# Power_Supply.net
KiCad netlist of a schematic drawn in Altium Designer
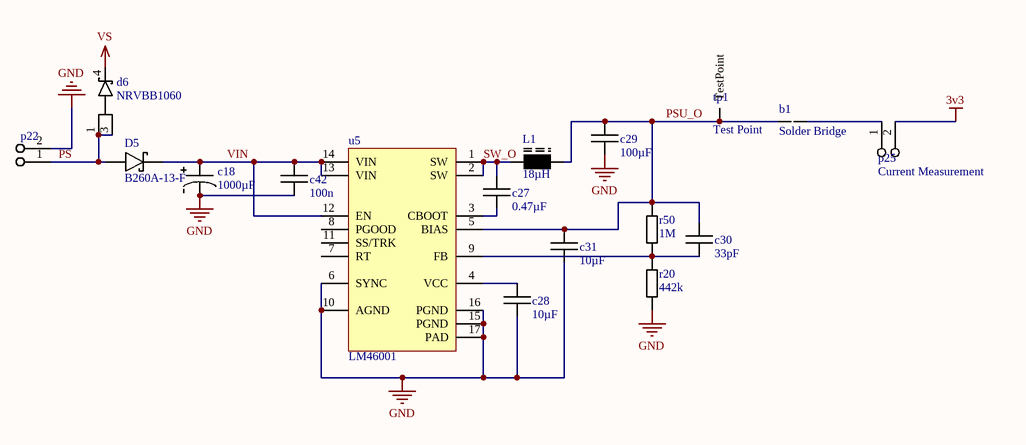
[diagram p0: Power Supply.SchDoc]

(export (version "E")
  (design (tool "Eeschema 10.0.6"))
  (components
    (comp (ref "b1")
      (value "Solder Bridge")
      (footprint "Solder Bridge")
      (libsource (lib "Board_Props") (part "Solder Bridge"))
    )
    (comp (ref "c18")
      (value "1000µF")
      (footprint "TH Elco 16")
      (description "d = 16mm")
      (libsource (lib "Panasonic") (part "Elco TH d16"))
    )
    (comp (ref "c27")
      (value "0.47µF")
      (footprint "0805")
      (description "...F")
      (libsource (lib "Generic R-C") (part "0805 Capacitor"))
    )
    (comp (ref "c28")
      (value "10µF")
      (footprint "0603")
      (description "...F")
      (libsource (lib "Generic R-C") (part "0603 Capacitor"))
    )
    (comp (ref "c29")
      (value "100µF")
      (footprint "1210")
      (description "C1210C107M8PACTU")
      (libsource (lib "KEMET MLCC") (part "1210 Capacitor"))
    )
    (comp (ref "c30")
      (value "33pF")
      (footprint "0603")
      (description "...F")
      (libsource (lib "Generic R-C") (part "0603 Capacitor"))
    )
    (comp (ref "c31")
      (value "10µF")
      (footprint "0603")
      (description "...F")
      (libsource (lib "Generic R-C") (part "0603 Capacitor"))
    )
    (comp (ref "c42")
      (value "100n")
      (footprint "0603")
      (description "...F")
      (libsource (lib "Generic R-C") (part "0603 Capacitor"))
    )
    (comp (ref "D5")
      (value "B260A-13-F")
      (footprint "DO-214AB (SMA)")
      (description "Schottky Rectifier")
      (libsource (lib "Diodes_inc") (part "B260A-13-F"))
    )
    (comp (ref "d6")
      (value "NRVBB1060")
      (footprint "D²PAK 3")
      (description "Schottky Diode 10A")
      (libsource (lib "ON Semiconductor") (part "NRVBB1060"))
    )
    (comp (ref "L1")
      (value "18µH")
      (footprint "SMD Inductor 7.4x7.4")
      (description "Shielded Power Inducor")
      (libsource (lib "Bourns") (part "SRR0735A-180M"))
    )
    (comp (ref "p22")
      (value "MKDSN 1.5")
      (footprint "ScrewWtB-2")
      (description "Wire-to-board connection")
      (libsource (lib "Phoenix Contact") (part "MKDSN 1.5"))
    )
    (comp (ref "p25")
      (value "Current Measurement")
      (footprint "1x2-HeaderPin")
      (description "2 Pin Header")
      (libsource (lib "Multicomp") (part "2 Pin Header"))
    )
    (comp (ref "r20")
      (value "442k")
      (footprint "0603")
      (description "...R")
      (libsource (lib "Generic R-C") (part "0603 Resistor"))
    )
    (comp (ref "r50")
      (value "1M")
      (footprint "0603")
      (description "...R")
      (libsource (lib "Generic R-C") (part "0603 Resistor"))
    )
    (comp (ref "tp1")
      (value "Test Point")
      (footprint "Test Point")
      (libsource (lib "Board_Props") (part "Test Point"))
    )
    (comp (ref "u5")
      (value "LM46001")
      (footprint "PWP0016G")
      (libsource (lib "Texas Instruments") (part "LM46001"))
    )
  )
  (nets
    (net (code "1") (name "/PS") (class "Default")
      (node (ref "D5") (pin "2") (pinfunction "Anode_2") (pintype "passive"))
      (node (ref "d6") (pin "1") (pintype "passive"))
      (node (ref "d6") (pin "3") (pintype "passive"))
      (node (ref "p22") (pin "1") (pinfunction "1_1") (pintype "passive"))
    )
    (net (code "2") (name "/PSU_O") (class "Default")
      (node (ref "L1") (pin "2") (pinfunction "2_2") (pintype "passive"))
      (node (ref "b1") (pin "1") (pinfunction "1_1") (pintype "passive"))
      (node (ref "c29") (pin "2") (pinfunction "2_2") (pintype "passive"))
      (node (ref "c30") (pin "2") (pinfunction "2_2") (pintype "passive"))
      (node (ref "c31") (pin "2") (pinfunction "2_2") (pintype "passive"))
      (node (ref "r50") (pin "1") (pintype "passive"))
      (node (ref "tp1") (pin "1") (pinfunction "TestPoint_1") (pintype "passive"))
      (node (ref "u5") (pin "5") (pinfunction "BIAS_5") (pintype "power_in"))
    )
    (net (code "3") (name "/SW_O") (class "Default")
      (node (ref "L1") (pin "1") (pinfunction "1_1") (pintype "passive"))
      (node (ref "c27") (pin "2") (pintype "passive"))
      (node (ref "u5") (pin "1") (pinfunction "SW_1") (pintype "power_in"))
      (node (ref "u5") (pin "2") (pinfunction "SW_2") (pintype "power_in"))
    )
    (net (code "4") (name "/VIN") (class "Default")
      (node (ref "D5") (pin "1") (pinfunction "Kathode_1") (pintype "passive"))
      (node (ref "c18") (pin "2") (pintype "passive"))
      (node (ref "c42") (pin "2") (pinfunction "2_2") (pintype "passive"))
      (node (ref "u5") (pin "12") (pinfunction "EN_12") (pintype "passive"))
      (node (ref "u5") (pin "13") (pinfunction "VIN_13") (pintype "power_in"))
      (node (ref "u5") (pin "14") (pinfunction "VIN_14") (pintype "power_in"))
    )
    (net (code "5") (name "3v3") (class "Default")
      (node (ref "p25") (pin "2") (pinfunction "2_2") (pintype "passive"))
    )
    (net (code "6") (name "GND") (class "Default")
      (node (ref "c18") (pin "1") (pintype "passive"))
      (node (ref "c28") (pin "1") (pinfunction "1_1") (pintype "passive"))
      (node (ref "c29") (pin "1") (pinfunction "1_1") (pintype "passive"))
      (node (ref "c31") (pin "1") (pinfunction "1_1") (pintype "passive"))
      (node (ref "c42") (pin "1") (pinfunction "1_1") (pintype "passive"))
      (node (ref "p22") (pin "2") (pinfunction "2_2") (pintype "passive"))
      (node (ref "r20") (pin "1") (pintype "passive"))
      (node (ref "u5") (pin "10") (pinfunction "AGND_10") (pintype "power_in"))
      (node (ref "u5") (pin "15") (pinfunction "PGND_15") (pintype "power_in"))
      (node (ref "u5") (pin "16") (pinfunction "PGND_16") (pintype "power_in"))
      (node (ref "u5") (pin "17") (pinfunction "PAD_17") (pintype "power_in"))
      (node (ref "u5") (pin "6") (pinfunction "SYNC_6") (pintype "passive"))
    )
    (net (code "7") (name "Net-(b1-Pad2)") (class "Default")
      (node (ref "b1") (pin "2") (pinfunction "2_2") (pintype "passive"))
      (node (ref "p25") (pin "1") (pinfunction "1_1") (pintype "passive"))
    )
    (net (code "8") (name "Net-(u5-CBOOT)") (class "Default")
      (node (ref "c27") (pin "1") (pintype "passive"))
      (node (ref "u5") (pin "3") (pinfunction "CBOOT_3") (pintype "power_in"))
    )
    (net (code "9") (name "Net-(u5-FB)") (class "Default")
      (node (ref "c30") (pin "1") (pinfunction "1_1") (pintype "passive"))
      (node (ref "r20") (pin "2") (pintype "passive"))
      (node (ref "r50") (pin "2") (pintype "passive"))
      (node (ref "u5") (pin "9") (pinfunction "FB_9") (pintype "power_in"))
    )
    (net (code "10") (name "Net-(u5-VCC)") (class "Default")
      (node (ref "c28") (pin "2") (pinfunction "2_2") (pintype "passive"))
      (node (ref "u5") (pin "4") (pinfunction "VCC_4") (pintype "power_in"))
    )
    (net (code "11") (name "PGND") (class "Default")
      (node (ref "u5") (pin "16") (pinfunction "PGND_16") (pintype "power_in"))
    )
    (net (code "12") (name "SW") (class "Default")
      (node (ref "u5") (pin "2") (pinfunction "SW_2") (pintype "power_in"))
    )
    (net (code "13") (name "VS") (class "Default") (node (ref "d6") (pin "4") (pintype "passive")))
    (net (code "14") (name "Vin") (class "Default")
      (node (ref "u5") (pin "14") (pinfunction "Vin_14") (pintype "power_in"))
    )
    (net (code "15") (name "unconnected-(u5-PGOOD-Pad8)") (class "Default")
      (node (ref "u5") (pin "8") (pinfunction "PGOOD_8") (pintype "passive"))
    )
    (net (code "16") (name "unconnected-(u5-RT-Pad7)") (class "Default")
      (node (ref "u5") (pin "7") (pinfunction "RT_7") (pintype "passive"))
    )
    (net (code "17") (name "unconnected-(u5-SS{slash}TRK-Pad11)") (class "Default")
      (node (ref "u5") (pin "11") (pinfunction "SS/TRK_11") (pintype "passive"))
    )
  )
)
